# REF5040.net
KiCad netlist of a schematic drawn in Altium Designer
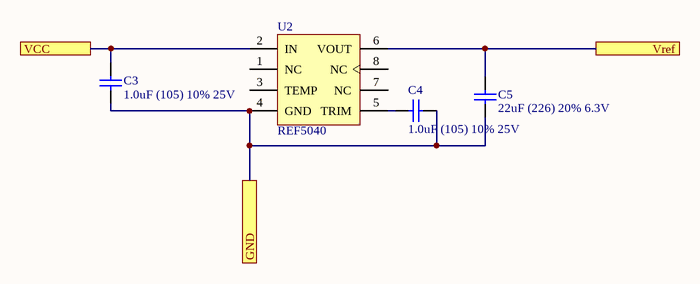
[diagram p0: REF5040.SchDoc]

(export (version "E")
  (design (tool "Eeschema 10.0.6"))
  (components
    (comp (ref "C3")
      (value "1.0uF (105) 10% 25V")
      (footprint "0402_C")
      (description "贴片电容")
      (libsource (lib "Miscellaneous Devices LC") (part "0402 1.0uF (105) 10% 25V"))
    )
    (comp (ref "C4")
      (value "1.0uF (105) 10% 25V")
      (footprint "0402_C")
      (description "贴片电容")
      (libsource (lib "Miscellaneous Devices LC") (part "0402 1.0uF (105) 10% 25V"))
    )
    (comp (ref "C5")
      (value "22uF (226) 20% 6.3V")
      (footprint "0603_C")
      (description "贴片电容")
      (libsource (lib "Miscellaneous Devices LC") (part "0603 22uF (226) 20% 6.3V"))
    )
    (comp (ref "U2")
      (value "REF5040")
      (footprint "SOP8_N")
      (description "高精度电压基准")
      (fields (field (name "版权归属") "源创客"))
      (libsource (lib "1.3   - 电源类芯片") (part "REF5040"))
    )
  )
  (nets
    (net (code "1") (name "/GND") (class "Default")
      (node (ref "C3") (pin "1") (pinfunction "1_1") (pintype "passive"))
      (node (ref "C4") (pin "2") (pinfunction "2_2") (pintype "passive"))
      (node (ref "C5") (pin "1") (pinfunction "1_1") (pintype "passive"))
      (node (ref "U2") (pin "4") (pinfunction "GND_4") (pintype "passive"))
    )
    (net (code "2") (name "/VCC") (class "Default")
      (node (ref "C3") (pin "2") (pinfunction "2_2") (pintype "passive"))
      (node (ref "U2") (pin "2") (pinfunction "IN_2") (pintype "passive"))
    )
    (net (code "3") (name "/Vref") (class "Default")
      (node (ref "C5") (pin "2") (pinfunction "2_2") (pintype "passive"))
      (node (ref "U2") (pin "6") (pinfunction "VOUT_6") (pintype "passive"))
    )
    (net (code "4") (name "Net-(U2-TRIM)") (class "Default")
      (node (ref "C4") (pin "1") (pinfunction "1_1") (pintype "passive"))
      (node (ref "U2") (pin "5") (pinfunction "TRIM_5") (pintype "passive"))
    )
    (net (code "5") (name "unconnected-(U2-NC-Pad1)") (class "Default")
      (node (ref "U2") (pin "1") (pinfunction "NC_1") (pintype "passive"))
    )
    (net (code "6") (name "unconnected-(U2-NC-Pad7)") (class "Default")
      (node (ref "U2") (pin "7") (pinfunction "NC_7") (pintype "passive"))
    )
    (net (code "7") (name "unconnected-(U2-NC-Pad8)") (class "Default")
      (node (ref "U2") (pin "8") (pinfunction "NC_8") (pintype "passive"))
    )
    (net (code "8") (name "unconnected-(U2-TEMP-Pad3)") (class "Default")
      (node (ref "U2") (pin "3") (pinfunction "TEMP_3") (pintype "passive"))
    )
  )
)
